# ir_led.net
KiCad netlist of a schematic drawn in EAGLE
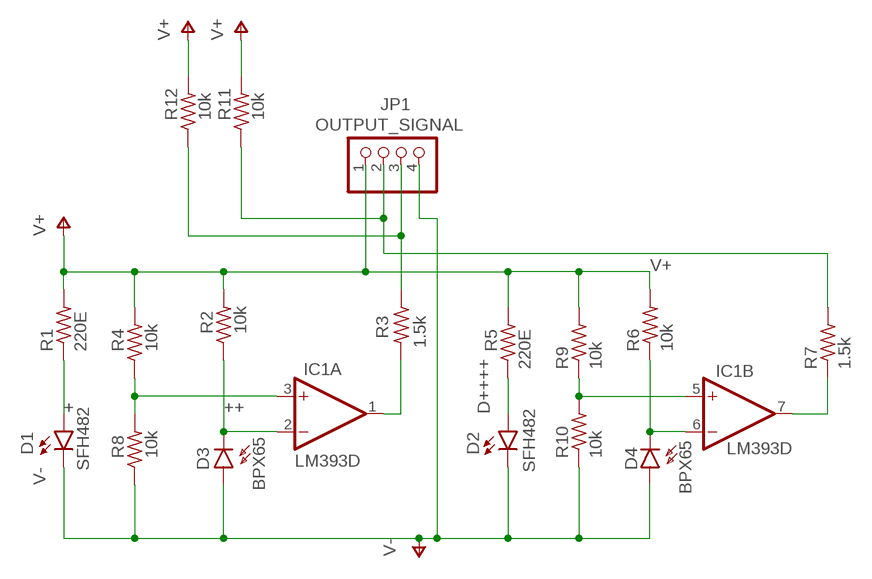
[diagram p0: schematic, sheet 1]

(export (version "E")
  (design (tool "Eeschema 10.0.6"))
  (components
    (comp (ref "D1")
      (value "SFH482")
      (footprint "eagle-import:SFH482")
      (libsource (lib "eagle-import") (part "SFH482"))
    )
    (comp (ref "D2")
      (value "SFH482")
      (footprint "eagle-import:SFH482")
      (libsource (lib "eagle-import") (part "SFH482"))
    )
    (comp (ref "D3")
      (value "BPX65")
      (footprint "eagle-import:BPX65")
      (fields (field (name "MPN") "BPX65."))
      (libsource (lib "eagle-import") (part "BPX65"))
    )
    (comp (ref "D4")
      (value "BPX65")
      (footprint "eagle-import:BPX65")
      (fields (field (name "MPN") "BPX65."))
      (libsource (lib "eagle-import") (part "BPX65"))
    )
    (comp (ref "IC1")
      (value "LM393D")
      (footprint "eagle-import:SO08")
      (libsource (lib "eagle-import") (part "LM393D"))
    )
    (comp (ref "JP1")
      (value "OUTPUT_SIGNAL")
      (footprint "eagle-import:1X04")
      (libsource (lib "eagle-import") (part "PINHD-1X4"))
    )
    (comp (ref "R1")
      (value "220E")
      (footprint "eagle-import:0204_7")
      (libsource (lib "eagle-import") (part "R-US_0204/7"))
    )
    (comp (ref "R2")
      (value "10k")
      (footprint "eagle-import:0204_7")
      (libsource (lib "eagle-import") (part "R-US_0204/7"))
    )
    (comp (ref "R3")
      (value "1.5k")
      (footprint "eagle-import:0204_7")
      (libsource (lib "eagle-import") (part "R-US_0204/7"))
    )
    (comp (ref "R4")
      (value "10k")
      (footprint "eagle-import:0204_7")
      (libsource (lib "eagle-import") (part "R-US_0204/7"))
    )
    (comp (ref "R5")
      (value "220E")
      (footprint "eagle-import:0204_7")
      (libsource (lib "eagle-import") (part "R-US_0204/7"))
    )
    (comp (ref "R6")
      (value "10k")
      (footprint "eagle-import:0204_7")
      (libsource (lib "eagle-import") (part "R-US_0204/7"))
    )
    (comp (ref "R7")
      (value "1.5k")
      (footprint "eagle-import:0204_7")
      (libsource (lib "eagle-import") (part "R-US_0204/7"))
    )
    (comp (ref "R8")
      (value "10k")
      (footprint "eagle-import:0204_7")
      (libsource (lib "eagle-import") (part "R-US_0204/7"))
    )
    (comp (ref "R9")
      (value "10k")
      (footprint "eagle-import:0204_7")
      (libsource (lib "eagle-import") (part "R-US_0204/7"))
    )
    (comp (ref "R10")
      (value "10k")
      (footprint "eagle-import:0204_7")
      (libsource (lib "eagle-import") (part "R-US_0204/7"))
    )
    (comp (ref "R11")
      (value "10k")
      (footprint "eagle-import:0204_7")
      (libsource (lib "eagle-import") (part "R-US_0204/7"))
    )
    (comp (ref "R12")
      (value "10k")
      (footprint "eagle-import:0204_7")
      (libsource (lib "eagle-import") (part "R-US_0204/7"))
    )
  )
  (nets
    (net (code "1") (name "/+") (class "Default")
      (node (ref "D1") (pin "A") (pinfunction "A_A") (pintype "passive"))
      (node (ref "R1") (pin "1") (pinfunction "1_1") (pintype "passive"))
    )
    (net (code "2") (name "/++") (class "Default")
      (node (ref "D3") (pin "K") (pinfunction "C_K") (pintype "passive"))
      (node (ref "IC1") (pin "2") (pinfunction "-IN_2") (pintype "input"))
      (node (ref "R2") (pin "1") (pinfunction "1_1") (pintype "passive"))
    )
    (net (code "3") (name "/D++++") (class "Default")
      (node (ref "D2") (pin "A") (pinfunction "A_A") (pintype "passive"))
      (node (ref "R5") (pin "1") (pinfunction "1_1") (pintype "passive"))
    )
    (net (code "4") (name "Net-(D4-C)") (class "Default")
      (node (ref "D4") (pin "K") (pinfunction "C_K") (pintype "passive"))
      (node (ref "IC1") (pin "6") (pinfunction "-IN_6") (pintype "input"))
      (node (ref "R6") (pin "1") (pinfunction "1_1") (pintype "passive"))
    )
    (net (code "5") (name "Net-(IC1A-+IN)") (class "Default")
      (node (ref "IC1") (pin "3") (pinfunction "+IN_3") (pintype "input"))
      (node (ref "R4") (pin "1") (pinfunction "1_1") (pintype "passive"))
      (node (ref "R8") (pin "2") (pinfunction "2_2") (pintype "passive"))
    )
    (net (code "6") (name "Net-(IC1A-OUT)") (class "Default")
      (node (ref "IC1") (pin "1") (pinfunction "OUT_1") (pintype "output"))
      (node (ref "R3") (pin "2") (pinfunction "2_2") (pintype "passive"))
    )
    (net (code "7") (name "Net-(IC1B-+IN)") (class "Default")
      (node (ref "IC1") (pin "5") (pinfunction "+IN_5") (pintype "input"))
      (node (ref "R10") (pin "2") (pinfunction "2_2") (pintype "passive"))
      (node (ref "R9") (pin "1") (pinfunction "1_1") (pintype "passive"))
    )
    (net (code "8") (name "Net-(IC1B-OUT)") (class "Default")
      (node (ref "IC1") (pin "7") (pinfunction "OUT_7") (pintype "output"))
      (node (ref "R7") (pin "1") (pinfunction "1_1") (pintype "passive"))
    )
    (net (code "9") (name "Net-(JP1-Pad2)") (class "Default")
      (node (ref "JP1") (pin "2") (pinfunction "2_2") (pintype "passive"))
      (node (ref "R11") (pin "1") (pinfunction "1_1") (pintype "passive"))
      (node (ref "R7") (pin "2") (pinfunction "2_2") (pintype "passive"))
    )
    (net (code "10") (name "Net-(JP1-Pad3)") (class "Default")
      (node (ref "JP1") (pin "3") (pinfunction "3_3") (pintype "passive"))
      (node (ref "R12") (pin "1") (pinfunction "1_1") (pintype "passive"))
      (node (ref "R3") (pin "1") (pinfunction "1_1") (pintype "passive"))
    )
    (net (code "11") (name "V+") (class "Default")
      (node (ref "JP1") (pin "1") (pinfunction "1_1") (pintype "passive"))
      (node (ref "R1") (pin "2") (pinfunction "2_2") (pintype "passive"))
      (node (ref "R11") (pin "2") (pinfunction "2_2") (pintype "passive"))
      (node (ref "R12") (pin "2") (pinfunction "2_2") (pintype "passive"))
      (node (ref "R2") (pin "2") (pinfunction "2_2") (pintype "passive"))
      (node (ref "R4") (pin "2") (pinfunction "2_2") (pintype "passive"))
      (node (ref "R5") (pin "2") (pinfunction "2_2") (pintype "passive"))
      (node (ref "R6") (pin "2") (pinfunction "2_2") (pintype "passive"))
      (node (ref "R9") (pin "2") (pinfunction "2_2") (pintype "passive"))
    )
    (net (code "12") (name "V-") (class "Default")
      (node (ref "D1") (pin "K") (pinfunction "C_K") (pintype "passive"))
      (node (ref "D2") (pin "K") (pinfunction "C_K") (pintype "passive"))
      (node (ref "D3") (pin "A") (pinfunction "A_A") (pintype "passive"))
      (node (ref "D4") (pin "A") (pinfunction "A_A") (pintype "passive"))
      (node (ref "JP1") (pin "4") (pinfunction "4_4") (pintype "passive"))
      (node (ref "R10") (pin "1") (pinfunction "1_1") (pintype "passive"))
      (node (ref "R8") (pin "1") (pinfunction "1_1") (pintype "passive"))
    )
  )
)
